# Gate_Drive.net
KiCad netlist of a schematic drawn in Altium Designer
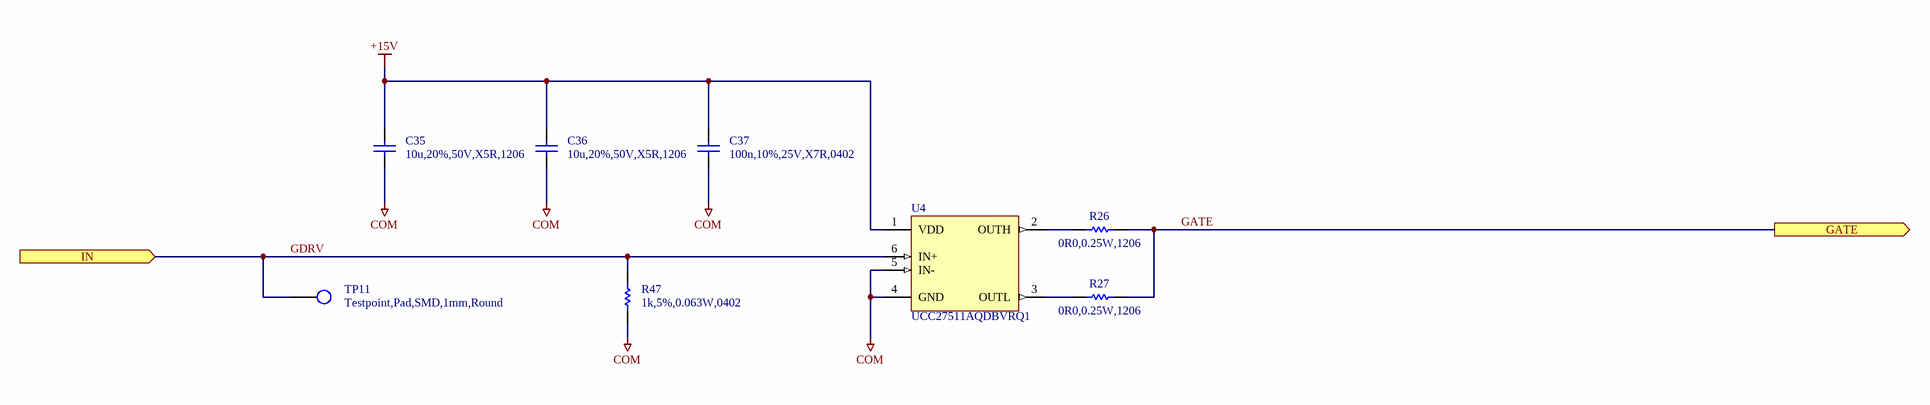
[diagram p0: Gate Drive.SchDoc]

(export (version "E")
  (design (tool "Eeschema 10.0.6"))
  (components
    (comp (ref "C35")
      (value "10u,20%,50V,X5R,1206")
      (footprint "CAPC3216X16N")
      (description "10ï¿½F ï¿½20% 50V Ceramic Capacitor X5R 1206 (3216 Metric)")
      (fields
        (field (name "MANUFACTURER 1 PART NUMBER") "CL31A106MBHNNNE")
        (field (name "VENDOR 1 PART NUMBER") "1276-6736-1-ND")
        (field (name "CREATEDBY") "Judd Foster")
      )
      (libsource (lib "Component Library") (part "CAP,Cer,10uF,50VDC,X5R,1206"))
    )
    (comp (ref "C36")
      (value "10u,20%,50V,X5R,1206")
      (footprint "CAPC3216X16N")
      (description "10ï¿½F ï¿½20% 50V Ceramic Capacitor X5R 1206 (3216 Metric)")
      (fields
        (field (name "MANUFACTURER 1 PART NUMBER") "CL31A106MBHNNNE")
        (field (name "VENDOR 1 PART NUMBER") "1276-6736-1-ND")
        (field (name "CREATEDBY") "Judd Foster")
      )
      (libsource (lib "Component Library") (part "CAP,Cer,10uF,50VDC,X5R,1206"))
    )
    (comp (ref "C37")
      (value "100n,10%,25V,X7R,0402")
      (footprint "CAPC1005X06N")
      (description "0.1ï¿½F ï¿½10% 25V Ceramic Capacitor X7R 0402 (1005 Metric)")
      (fields
        (field (name "MANUFACTURER 1 PART NUMBER") "GRM155R71E104KE14J")
        (field (name "VENDOR 1 PART NUMBER") "490-14603-1-ND")
        (field (name "CREATEDBY") "Judd Foster")
      )
      (libsource (lib "Component Library") (part "CAP,Cer,100nF,10%,25V,X7R,0402"))
    )
    (comp (ref "R26")
      (value "0R0,0.25W,1206")
      (footprint "RESC3216X06N")
      (description "0 Ohms Jumper Chip Resistor 1206 (3216 Metric) Automotive AEC-Q200 Thick Film")
      (fields
        (field (name "MANUFACTURER 1 PART NUMBER") "RMCF1206ZT0R00")
        (field (name "VENDOR 1 PART NUMBER") "RMCF1206ZT0R00CT-ND")
        (field (name "CREATEDBY") "Judd Foster")
      )
      (libsource (lib "Component Library") (part "RES,0R0,0.25W,1206"))
    )
    (comp (ref "R27")
      (value "0R0,0.25W,1206")
      (footprint "RESC3216X06N")
      (description "0 Ohms Jumper Chip Resistor 1206 (3216 Metric) Automotive AEC-Q200 Thick Film")
      (fields
        (field (name "MANUFACTURER 1 PART NUMBER") "RMCF1206ZT0R00")
        (field (name "VENDOR 1 PART NUMBER") "RMCF1206ZT0R00CT-ND")
        (field (name "CREATEDBY") "Judd Foster")
      )
      (libsource (lib "Component Library") (part "RES,0R0,0.25W,1206"))
    )
    (comp (ref "R47")
      (value "1k,5%,0.063W,0402")
      (footprint "RESC1005X04N")
      (description "1 kOhms ï¿½5% 0.063W, 1/16W Chip Resistor 0402 (1005 Metric) Automotive AEC-Q200 Thick Film")
      (fields
        (field (name "MANUFACTURER 1 PART NUMBER") "RMCF0402JT1K00")
        (field (name "VENDOR 1 PART NUMBER") "RMCF0402JT1K00CT-ND")
        (field (name "CREATEDBY") "Judd Foster")
      )
      (libsource (lib "Component Library") (part "RES,1k,5%,0.063W,0402"))
    )
    (comp (ref "TP11")
      (value "Testpoint,Pad,SMD,1mm,Round")
      (footprint "TP100")
      (description "PCB Testpoint 1mm Round")
      (fields (field (name "CREATEDBY") "Judd Foster"))
      (libsource (lib "Component Library") (part "Testpoint,Pad,SMD"))
    )
    (comp (ref "U4")
      (value "UCC27511AQDBVRQ1")
      (footprint "SOTFL95P260X145-6")
      (description "Gate Drivers Sngl-Ch high-Spd Low-Side Gate Driver")
      (fields
        (field (name "VENDOR 1 PART NUMBER") "595-UCC27511AQDBVRQ1")
        (field (name "CREATEDBY") "Judd Foster")
      )
      (libsource (lib "Component Library") (part "UCC27511AQDBVRQ1"))
    )
  )
  (nets
    (net (code "1") (name "+15V") (class "Default")
      (node (ref "C35") (pin "2") (pinfunction "2_2") (pintype "passive"))
      (node (ref "C36") (pin "2") (pinfunction "2_2") (pintype "passive"))
      (node (ref "C37") (pin "2") (pinfunction "2_2") (pintype "passive"))
      (node (ref "U4") (pin "1") (pinfunction "VDD_1") (pintype "power_in"))
    )
    (net (code "2") (name "/GATE") (class "Default")
      (node (ref "R26") (pin "2") (pinfunction "2_2") (pintype "passive"))
      (node (ref "R27") (pin "2") (pinfunction "2_2") (pintype "passive"))
    )
    (net (code "3") (name "/GDRV") (class "Default")
      (node (ref "R47") (pin "2") (pinfunction "2_2") (pintype "passive"))
      (node (ref "TP11") (pin "1") (pinfunction "TP_1") (pintype "passive"))
      (node (ref "U4") (pin "6") (pinfunction "IN+_6") (pintype "input"))
    )
    (net (code "4") (name "COM") (class "Default")
      (node (ref "C35") (pin "1") (pinfunction "1_1") (pintype "passive"))
      (node (ref "C36") (pin "1") (pinfunction "1_1") (pintype "passive"))
      (node (ref "C37") (pin "1") (pinfunction "1_1") (pintype "passive"))
      (node (ref "R47") (pin "1") (pinfunction "1_1") (pintype "passive"))
      (node (ref "U4") (pin "4") (pinfunction "GND_4") (pintype "power_in"))
      (node (ref "U4") (pin "5") (pinfunction "IN-_5") (pintype "input"))
    )
    (net (code "5") (name "Net-(U4-OUTH)") (class "Default")
      (node (ref "R26") (pin "1") (pinfunction "1_1") (pintype "passive"))
      (node (ref "U4") (pin "2") (pinfunction "OUTH_2") (pintype "output"))
    )
    (net (code "6") (name "Net-(U4-OUTL)") (class "Default")
      (node (ref "R27") (pin "1") (pinfunction "1_1") (pintype "passive"))
      (node (ref "U4") (pin "3") (pinfunction "OUTL_3") (pintype "output"))
    )
  )
)
